# CanTransceiver.net
KiCad netlist of a schematic drawn in Altium Designer
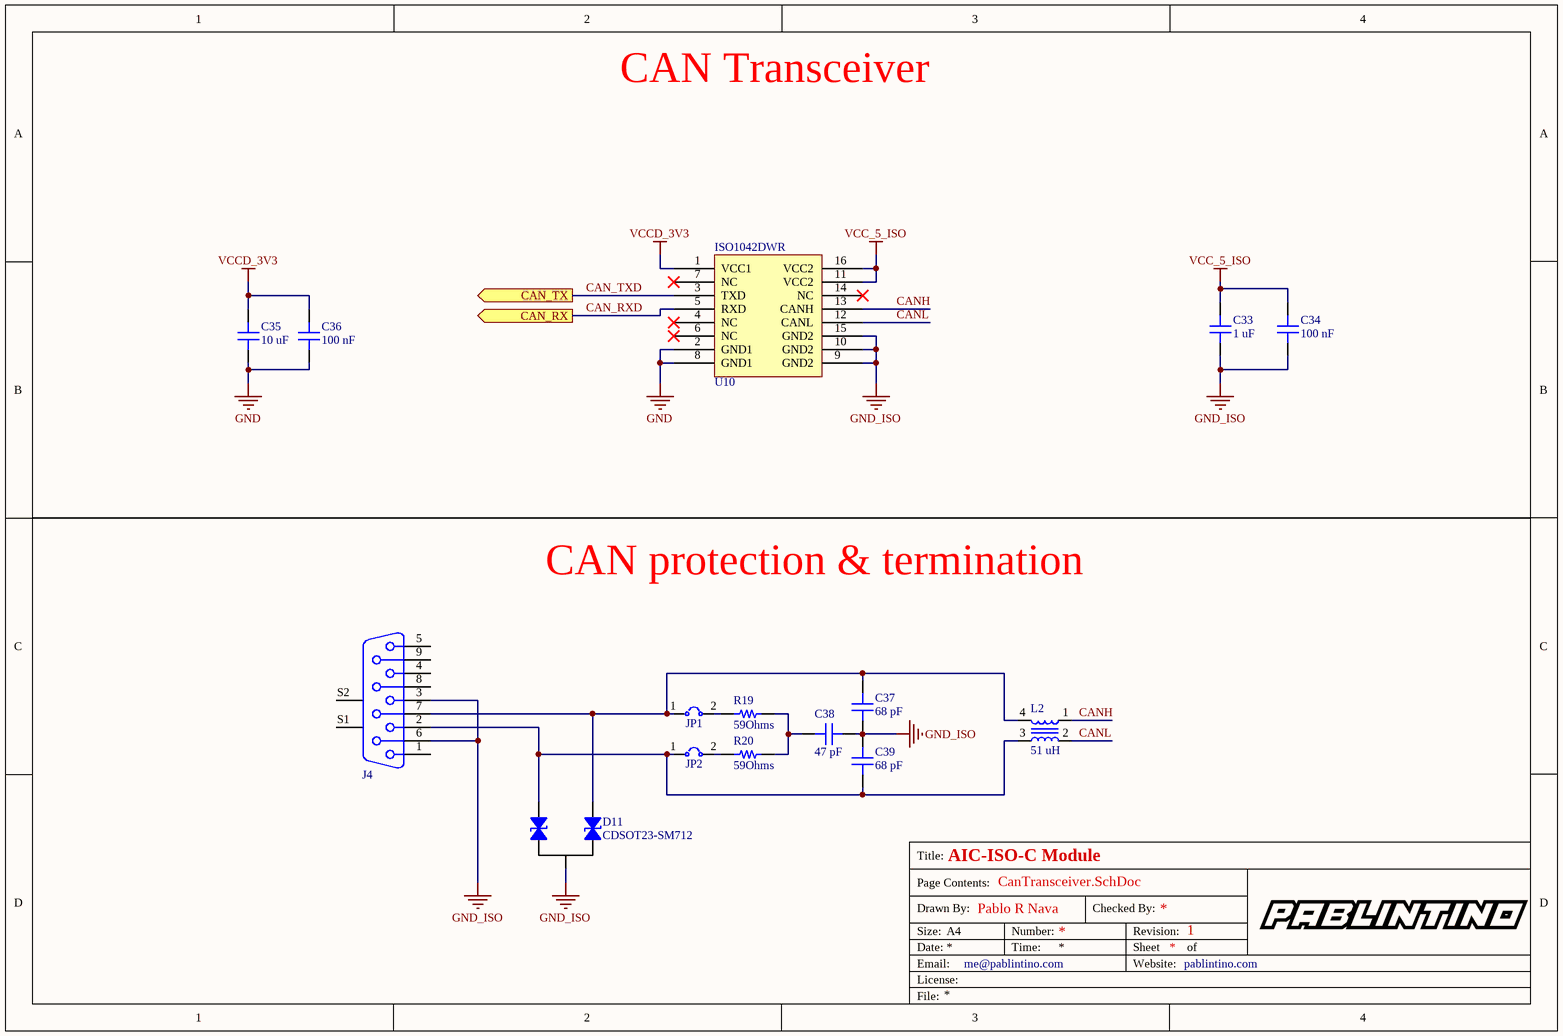
[diagram p0: CanTransceiver.SchDoc]

(export (version "E")
  (design (tool "Eeschema 10.0.6"))
  (components
    (comp (ref "C33")
      (value "1 uF")
      (footprint "CAP 0603_1608")
      (description "MLCC Ceramic 1 uF 25 V 10% Capacitor")
      (fields (field (name "PART NUMBER") "06033C105KAT4A") (field (name "MANUFACTURER") "AVX"))
      (libsource (lib "Database_Libs") (part "Capacitor"))
    )
    (comp (ref "C34")
      (value "100 nF")
      (footprint "CAP 0603_1608")
      (description "MLCC Ceramic 100 nF 16 V 10% Capacitor")
      (fields (field (name "PART NUMBER") "0603YC104KAT2A") (field (name "MANUFACTURER") "AVX"))
      (libsource (lib "Database_Libs") (part "Capacitor"))
    )
    (comp (ref "C35")
      (value "10 uF")
      (footprint "CAP 0805_2012")
      (description "MLCC Ceramic 10 uF 25 V 20% Capacitor")
      (fields (field (name "PART NUMBER") "0805YC106MAT2A") (field (name "MANUFACTURER") "AVX"))
      (libsource (lib "Database_Libs") (part "Capacitor"))
    )
    (comp (ref "C36")
      (value "100 nF")
      (footprint "CAP 0603_1608")
      (description "MLCC Ceramic 100 nF 50 V 10% Capacitor")
      (fields (field (name "PART NUMBER") "06035C104K4Z2A") (field (name "MANUFACTURER") "AVX"))
      (libsource (lib "Database_Libs") (part "Capacitor"))
    )
    (comp (ref "C37")
      (value "68 pF")
      (footprint "CAP 0603_1608")
      (description "MLCC Ceramic 68 pF 100 V 1% Capacitor")
      (fields (field (name "PART NUMBER") "06031A680FAT2A") (field (name "MANUFACTURER") "AVX"))
      (libsource (lib "Database_Libs") (part "Capacitor"))
    )
    (comp (ref "C38")
      (value "47 pF")
      (footprint "CAP 0603_1608")
      (description "MLCC Ceramic 47 pF 100 V 1% Capacitor")
      (fields (field (name "PART NUMBER") "06031U470FAT2A") (field (name "MANUFACTURER") "AVX"))
      (libsource (lib "Database_Libs") (part "Capacitor"))
    )
    (comp (ref "C39")
      (value "68 pF")
      (footprint "CAP 0603_1608")
      (description "MLCC Ceramic 68 pF 100 V 1% Capacitor")
      (fields (field (name "PART NUMBER") "06031A680FAT2A") (field (name "MANUFACTURER") "AVX"))
      (libsource (lib "Database_Libs") (part "Capacitor"))
    )
    (comp (ref "D11")
      (value "CDSOT23-SM712")
      (footprint "BOURNS SOT-23-3")
      (description "CAN bus TVS diode")
      (fields (field (name "MANUFACTURER") "Bourns"))
      (libsource (lib "Database_Libs") (part "DUAL TVS"))
    )
    (comp (ref "J4")
      (value "09681537613")
      (footprint "DSUB9")
      (description "DSUB SV FE SSDP ANG-US 09P AU3")
      (fields (field (name "MANUFACTURER") "Harting"))
      (libsource (lib "Database_Libs") (part "D Connector 9"))
    )
    (comp (ref "JP1")
      (value "61300211121")
      (footprint "JUMPER-100")
      (description "Connector Header Through Hole 2 position 0.100 (2.54mm)")
      (fields (field (name "MANUFACTURER") "Würth Elektronik"))
      (libsource (lib "Database_Libs") (part "JUMPER"))
    )
    (comp (ref "JP2")
      (value "61300211121")
      (footprint "JUMPER-100")
      (description "Connector Header Through Hole 2 position 0.100 (2.54mm)")
      (fields (field (name "MANUFACTURER") "Würth Elektronik"))
      (libsource (lib "Database_Libs") (part "JUMPER"))
    )
    (comp (ref "L2")
      (value "51 uH")
      (footprint "TDK_ACT45B")
      (description "CAN Bus Common Choke")
      (fields (field (name "PART NUMBER") "ACT45B-510-2P-TL003") (field (name "MANUFACTURER") "TDK"))
      (libsource (lib "Database_Libs") (part "Inductor"))
    )
    (comp (ref "R19")
      (value "59Ohms")
      (footprint "RES 1206_3216")
      (description "Thin Film Resistor 59 Ohms 1%")
      (fields (field (name "PART NUMBER") "CRCW120659R0FKEA") (field (name "MANUFACTURER") "Vishay / Dale"))
      (libsource (lib "Database_Libs") (part "Resistor"))
    )
    (comp (ref "R20")
      (value "59Ohms")
      (footprint "RES 1206_3216")
      (description "Thin Film Resistor 59 Ohms 1%")
      (fields (field (name "PART NUMBER") "CRCW120659R0FKEA") (field (name "MANUFACTURER") "Vishay / Dale"))
      (libsource (lib "Database_Libs") (part "Resistor"))
    )
    (comp (ref "U10")
      (value "ISO1042DWR")
      (footprint "TI-DW16_N")
      (description "Isolated CAN FD Transceiver")
      (fields (field (name "MANUFACTURER") "Texas Instruments"))
      (libsource (lib "Database_Libs") (part "ISO1042"))
    )
  )
  (nets
    (net (code "1") (name "/CANH") (class "Default")
      (node (ref "L2") (pin "1") (pinfunction "1_1") (pintype "passive"))
      (node (ref "U10") (pin "13") (pinfunction "CANH_13") (pintype "passive"))
    )
    (net (code "2") (name "/CANL") (class "Default")
      (node (ref "L2") (pin "2") (pinfunction "2_2") (pintype "passive"))
      (node (ref "U10") (pin "12") (pinfunction "CANL_12") (pintype "passive"))
    )
    (net (code "3") (name "/CAN_RXD") (class "Default")
      (node (ref "U10") (pin "5") (pinfunction "RXD_5") (pintype "passive"))
    )
    (net (code "4") (name "/CAN_TXD") (class "Default")
      (node (ref "U10") (pin "3") (pinfunction "TXD_3") (pintype "passive"))
    )
    (net (code "5") (name "GND") (class "Default")
      (node (ref "C35") (pin "2") (pinfunction "2_2") (pintype "passive"))
      (node (ref "C36") (pin "2") (pinfunction "2_2") (pintype "passive"))
      (node (ref "U10") (pin "2") (pinfunction "GND1_2") (pintype "passive"))
      (node (ref "U10") (pin "8") (pinfunction "GND1_8") (pintype "passive"))
    )
    (net (code "6") (name "GND_ISO") (class "Default")
      (node (ref "C33") (pin "1") (pinfunction "1_1") (pintype "passive"))
      (node (ref "C34") (pin "2") (pinfunction "2_2") (pintype "passive"))
      (node (ref "C37") (pin "2") (pinfunction "2_2") (pintype "passive"))
      (node (ref "C38") (pin "1") (pinfunction "1_1") (pintype "passive"))
      (node (ref "C39") (pin "1") (pinfunction "1_1") (pintype "passive"))
      (node (ref "D11") (pin "3") (pinfunction "3_3") (pintype "passive"))
      (node (ref "J4") (pin "3") (pinfunction "3_3") (pintype "passive"))
      (node (ref "J4") (pin "6") (pinfunction "6_6") (pintype "passive"))
      (node (ref "U10") (pin "10") (pinfunction "GND2_10") (pintype "passive"))
      (node (ref "U10") (pin "15") (pinfunction "GND2_15") (pintype "passive"))
      (node (ref "U10") (pin "9") (pinfunction "GND2_9") (pintype "passive"))
    )
    (net (code "7") (name "Net-(C38-Pad2)") (class "Default")
      (node (ref "C38") (pin "2") (pinfunction "2_2") (pintype "passive"))
      (node (ref "R19") (pin "1") (pinfunction "1_1") (pintype "passive"))
      (node (ref "R20") (pin "1") (pinfunction "1_1") (pintype "passive"))
    )
    (net (code "8") (name "Net-(JP1-A)") (class "Default")
      (node (ref "C37") (pin "1") (pinfunction "1_1") (pintype "passive"))
      (node (ref "D11") (pin "2") (pinfunction "2_2") (pintype "passive"))
      (node (ref "J4") (pin "7") (pinfunction "7_7") (pintype "passive"))
      (node (ref "JP1") (pin "1") (pinfunction "A_1") (pintype "passive"))
      (node (ref "L2") (pin "4") (pinfunction "4_4") (pintype "passive"))
    )
    (net (code "9") (name "Net-(JP1-K)") (class "Default")
      (node (ref "JP1") (pin "2") (pinfunction "K_2") (pintype "passive"))
      (node (ref "R19") (pin "2") (pinfunction "2_2") (pintype "passive"))
    )
    (net (code "10") (name "Net-(JP2-A)") (class "Default")
      (node (ref "C39") (pin "2") (pinfunction "2_2") (pintype "passive"))
      (node (ref "D11") (pin "1") (pinfunction "1_1") (pintype "passive"))
      (node (ref "J4") (pin "2") (pinfunction "2_2") (pintype "passive"))
      (node (ref "JP2") (pin "1") (pinfunction "A_1") (pintype "passive"))
      (node (ref "L2") (pin "3") (pinfunction "3_3") (pintype "passive"))
    )
    (net (code "11") (name "Net-(JP2-K)") (class "Default")
      (node (ref "JP2") (pin "2") (pinfunction "K_2") (pintype "passive"))
      (node (ref "R20") (pin "2") (pinfunction "2_2") (pintype "passive"))
    )
    (net (code "12") (name "VCCD_3V3") (class "Default")
      (node (ref "C35") (pin "1") (pinfunction "1_1") (pintype "passive"))
      (node (ref "C36") (pin "1") (pinfunction "1_1") (pintype "passive"))
      (node (ref "U10") (pin "1") (pinfunction "VCC1_1") (pintype "passive"))
    )
    (net (code "13") (name "VCC_5_ISO") (class "Default")
      (node (ref "C33") (pin "2") (pinfunction "2_2") (pintype "passive"))
      (node (ref "C34") (pin "1") (pinfunction "1_1") (pintype "passive"))
      (node (ref "U10") (pin "11") (pinfunction "VCC2_11") (pintype "passive"))
      (node (ref "U10") (pin "16") (pinfunction "VCC2_16") (pintype "passive"))
    )
    (net (code "14") (name "unconnected-(J4-Pad1)") (class "Default")
      (node (ref "J4") (pin "1") (pinfunction "1_1") (pintype "passive"))
    )
    (net (code "15") (name "unconnected-(J4-Pad4)") (class "Default")
      (node (ref "J4") (pin "4") (pinfunction "4_4") (pintype "passive"))
    )
    (net (code "16") (name "unconnected-(J4-Pad5)") (class "Default")
      (node (ref "J4") (pin "5") (pinfunction "5_5") (pintype "passive"))
    )
    (net (code "17") (name "unconnected-(J4-Pad8)") (class "Default")
      (node (ref "J4") (pin "8") (pinfunction "8_8") (pintype "passive"))
    )
    (net (code "18") (name "unconnected-(J4-Pad9)") (class "Default")
      (node (ref "J4") (pin "9") (pinfunction "9_9") (pintype "passive"))
    )
    (net (code "19") (name "unconnected-(J4-PadS1)") (class "Default")
      (node (ref "J4") (pin "S1") (pinfunction "S1_S1") (pintype "passive"))
    )
    (net (code "20") (name "unconnected-(J4-PadS2)") (class "Default")
      (node (ref "J4") (pin "S2") (pinfunction "S2_S2") (pintype "passive"))
    )
    (net (code "21") (name "unconnected-(U10-NC-Pad4)") (class "Default")
      (node (ref "U10") (pin "4") (pinfunction "NC_4") (pintype "passive+no_connect"))
    )
    (net (code "22") (name "unconnected-(U10-NC-Pad6)") (class "Default")
      (node (ref "U10") (pin "6") (pinfunction "NC_6") (pintype "passive+no_connect"))
    )
    (net (code "23") (name "unconnected-(U10-NC-Pad7)") (class "Default")
      (node (ref "U10") (pin "7") (pinfunction "NC_7") (pintype "passive+no_connect"))
    )
    (net (code "24") (name "unconnected-(U10-NC-Pad14)") (class "Default")
      (node (ref "U10") (pin "14") (pinfunction "NC_14") (pintype "passive+no_connect"))
    )
  )
)
